# Sheet2.net
KiCad netlist of a schematic drawn in Altium Designer
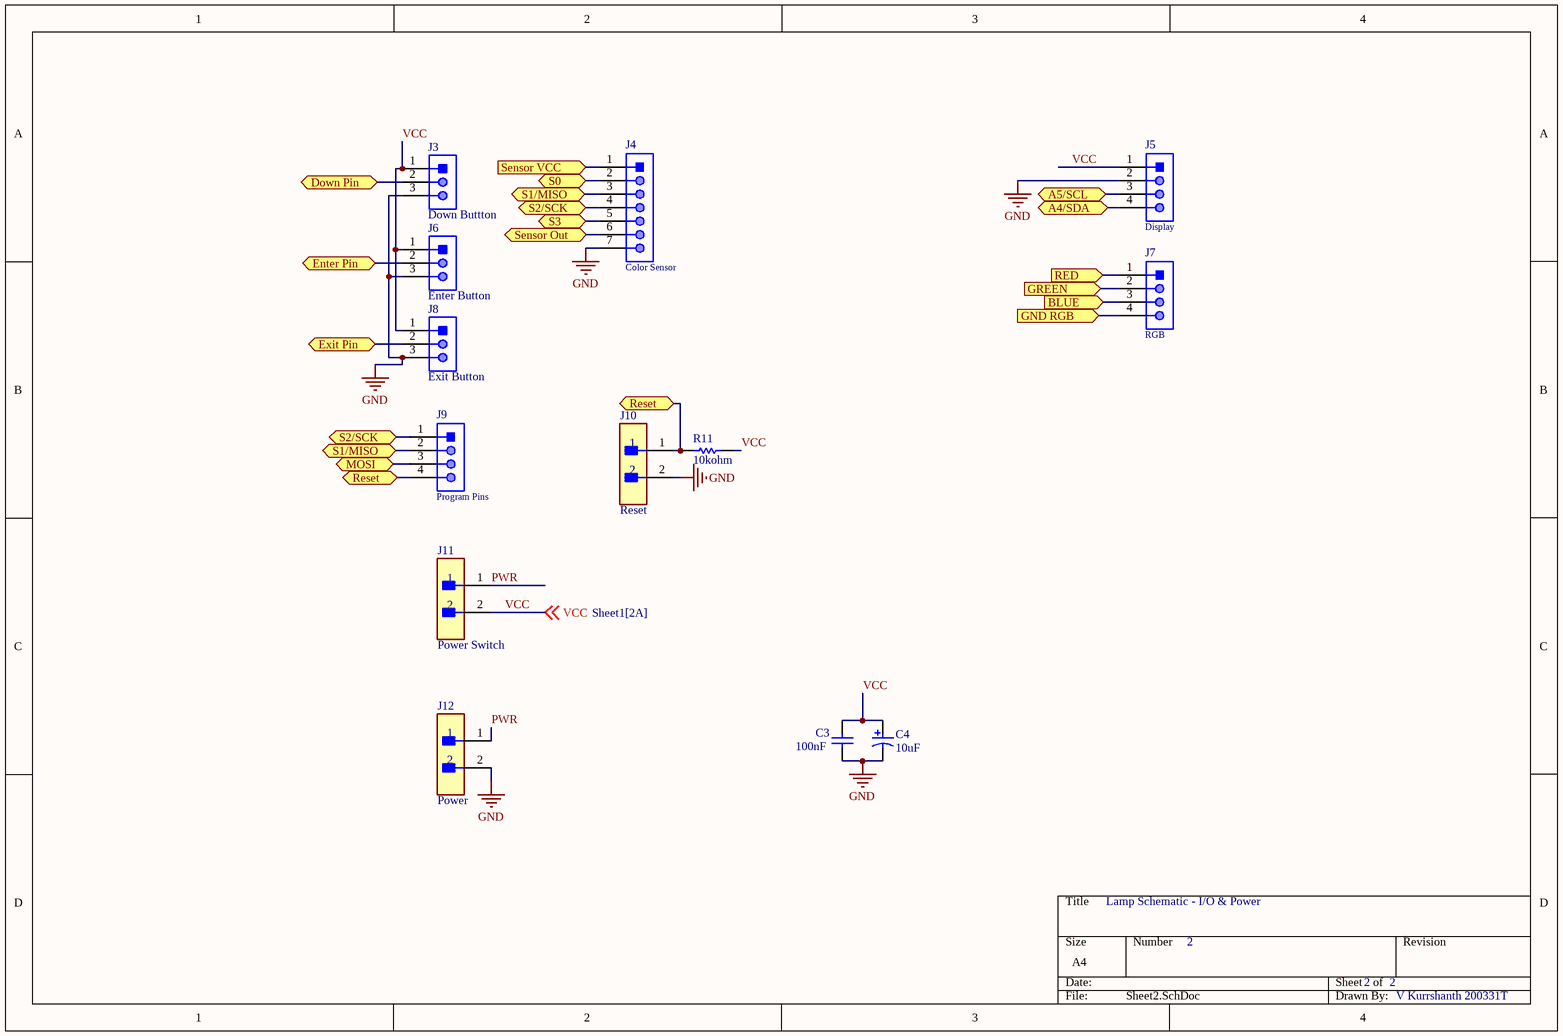
[diagram p0: Sheet2.SchDoc]

(export (version "E")
  (design (tool "Eeschema 10.0.6"))
  (components
    (comp (ref "C3")
      (value "100nF")
      (footprint "VISH-K104K15X7RF5TL2")
      (description "Ceramic Capacitor, 100 nF, +/- 10%, 50 V, -55 to 125 degC, 2-Pin THD, RoHS, Tape and Reel")
      (fields (field (name "MANUFACTURER") "Vishay") (field (name "TOLERANCE") "±10%"))
      (libsource (lib "Altium Content Vault") (part "CAP-NP-2"))
    )
    (comp (ref "C4")
      (value "10uF")
      (footprint "CAPPR55-200-1100X500X1200")
      (description "Aluminum Electrolytic Capacitor, 10 uF, +/- 20%, 50 V, -40 to 85 degC, 2-Pin THD, RoHS, Bulk")
      (fields (field (name "MANUFACTURER") "Panasonic") (field (name "TOLERANCE") "20%"))
      (libsource (lib "Altium Content Vault") (part "CAP-P-2"))
    )
    (comp (ref "J3")
      (value "Down Buttton")
      (footprint "MOLX-22-28-4033_V")
      (description "Male Header, Pitch 2.54 mm, 1 x 3 Position, Height 8.38 mm, Tail Length 3.18 mm, RoHS, Bulk")
      (fields (field (name "MANUFACTURER") "Molex"))
      (libsource (lib "Altium Content Vault") (part "CN-1P-M-R3"))
    )
    (comp (ref "J4")
      (value "Color Sensor")
      (footprint "61300711121")
      (description "THT Vertical Pin Header WR-PHD, Pitch 2.54 mm, Single Row, 7 pins")
      (fields
        (field (name "MANUFACTURER") "Wurth Elektronik")
        (field (name "PART NUMBER") "61300711121")
        (field (name "PUBLISHER") "WurthElektronik")
      )
      (libsource (lib "Altium Content Vault") (part "WE-CN-1P-M-R7"))
    )
    (comp (ref "J5")
      (value "Display")
      (footprint "61300411121")
      (description "THT Vertical Pin Header WR-PHD, Pitch 2.54 mm, Single Row, 4 pins")
      (fields
        (field (name "MANUFACTURER") "Wurth Elektronik")
        (field (name "PART NUMBER") "61300411121")
        (field (name "PUBLISHER") "WurthElektronik")
      )
      (libsource (lib "Altium Content Vault") (part "WE-CN-1P-M-R4"))
    )
    (comp (ref "J6")
      (value "Enter Button")
      (footprint "MOLX-22-28-4033_V")
      (description "Male Header, Pitch 2.54 mm, 1 x 3 Position, Height 8.38 mm, Tail Length 3.18 mm, RoHS, Bulk")
      (fields (field (name "MANUFACTURER") "Molex"))
      (libsource (lib "Altium Content Vault") (part "CN-1P-M-R3"))
    )
    (comp (ref "J7")
      (value "RGB")
      (footprint "61300411121")
      (description "THT Vertical Pin Header WR-PHD, Pitch 2.54 mm, Single Row, 4 pins")
      (fields
        (field (name "MANUFACTURER") "Wurth Elektronik")
        (field (name "PART NUMBER") "61300411121")
        (field (name "PUBLISHER") "WurthElektronik")
      )
      (libsource (lib "Altium Content Vault") (part "WE-CN-1P-M-R4"))
    )
    (comp (ref "J8")
      (value "Exit Button")
      (footprint "MOLX-22-28-4033_V")
      (description "Male Header, Pitch 2.54 mm, 1 x 3 Position, Height 8.38 mm, Tail Length 3.18 mm, RoHS, Bulk")
      (fields (field (name "MANUFACTURER") "Molex"))
      (libsource (lib "Altium Content Vault") (part "CN-1P-M-R3"))
    )
    (comp (ref "J9")
      (value "Program Pins")
      (footprint "61300411121")
      (description "THT Vertical Pin Header WR-PHD, Pitch 2.54 mm, Single Row, 4 pins")
      (fields
        (field (name "MANUFACTURER") "Wurth Elektronik")
        (field (name "PART NUMBER") "61300411121")
        (field (name "PUBLISHER") "WurthElektronik")
      )
      (libsource (lib "Altium Content Vault") (part "WE-CN-1P-M-R4"))
    )
    (comp (ref "J10")
      (value "Reset")
      (footprint "FP-M20-9990246-MFG")
      (description "CONN HEADER VERT 2POS 2.54MM")
      (fields
        (field (name "OCTOPART") "https://octopart.com/m20-9990246-harwin-2590635")
        (field (name "MANUFACTURER") "Harwin")
      )
      (libsource (lib "Altium Content Vault") (part "3bc925449376181038e59eaffc5286c"))
    )
    (comp (ref "J11")
      (value "Power Switch")
      (footprint "FP-M20-9990246-MFG")
      (description "CONN HEADER VERT 2POS 2.54MM")
      (fields
        (field (name "OCTOPART") "https://octopart.com/m20-9990246-harwin-2590635")
        (field (name "MANUFACTURER") "Harwin")
      )
      (libsource (lib "Altium Content Vault") (part "3bc925449376181038e59eaffc5286c"))
    )
    (comp (ref "J12")
      (value "Power")
      (footprint "FP-M20-9990246-MFG")
      (description "CONN HEADER VERT 2POS 2.54MM")
      (fields
        (field (name "OCTOPART") "https://octopart.com/m20-9990246-harwin-2590635")
        (field (name "MANUFACTURER") "Harwin")
      )
      (libsource (lib "Altium Content Vault") (part "3bc925449376181038e59eaffc5286c"))
    )
    (comp (ref "R11")
      (value "10kohm")
      (footprint "RESA60-630X240")
      (description "Axial Resistor, 10 KOhm, +/- 1%, 0.25 W, -55 to 155 degC, 2-Pin THD, RoHS, Bulk")
      (fields (field (name "TOLERANCE") "1%") (field (name "MANUFACTURER") "Yageo"))
      (libsource (lib "Altium Content Vault") (part "RES-2"))
    )
  )
  (nets
    (net (code "1") (name "/A4{slash}SDA") (class "Default")
      (node (ref "J5") (pin "4") (pinfunction "4_4") (pintype "passive"))
    )
    (net (code "2") (name "/A5{slash}SCL") (class "Default")
      (node (ref "J5") (pin "3") (pinfunction "3_3") (pintype "passive"))
    )
    (net (code "3") (name "/BLUE") (class "Default")
      (node (ref "J7") (pin "3") (pinfunction "3_3") (pintype "passive"))
    )
    (net (code "4") (name "/Down Pin") (class "Default")
      (node (ref "J3") (pin "2") (pinfunction "2_2") (pintype "passive"))
    )
    (net (code "5") (name "/Enter Pin") (class "Default")
      (node (ref "J6") (pin "2") (pinfunction "2_2") (pintype "passive"))
    )
    (net (code "6") (name "/Exit Pin") (class "Default")
      (node (ref "J8") (pin "2") (pinfunction "2_2") (pintype "passive"))
    )
    (net (code "7") (name "/GND RGB") (class "Default")
      (node (ref "J7") (pin "4") (pinfunction "4_4") (pintype "passive"))
    )
    (net (code "8") (name "/GREEN") (class "Default")
      (node (ref "J7") (pin "2") (pinfunction "2_2") (pintype "passive"))
    )
    (net (code "9") (name "/MOSI") (class "Default")
      (node (ref "J9") (pin "3") (pinfunction "3_3") (pintype "passive"))
    )
    (net (code "10") (name "/PWR") (class "Default")
      (node (ref "J11") (pin "1") (pinfunction "1_1") (pintype "passive"))
      (node (ref "J12") (pin "1") (pinfunction "1_1") (pintype "passive"))
    )
    (net (code "11") (name "/RED") (class "Default")
      (node (ref "J7") (pin "1") (pinfunction "1_1") (pintype "passive"))
    )
    (net (code "12") (name "/Reset") (class "Default")
      (node (ref "J10") (pin "1") (pinfunction "1_1") (pintype "passive"))
      (node (ref "J9") (pin "4") (pinfunction "4_4") (pintype "passive"))
      (node (ref "R11") (pin "1") (pinfunction "1_1") (pintype "passive"))
    )
    (net (code "13") (name "/S0") (class "Default")
      (node (ref "J4") (pin "2") (pinfunction "2_2") (pintype "passive"))
    )
    (net (code "14") (name "/S1{slash}MISO") (class "Default")
      (node (ref "J4") (pin "3") (pinfunction "3_3") (pintype "passive"))
      (node (ref "J9") (pin "2") (pinfunction "2_2") (pintype "passive"))
    )
    (net (code "15") (name "/S2{slash}SCK") (class "Default")
      (node (ref "J4") (pin "4") (pinfunction "4_4") (pintype "passive"))
      (node (ref "J9") (pin "1") (pinfunction "1_1") (pintype "passive"))
    )
    (net (code "16") (name "/S3") (class "Default")
      (node (ref "J4") (pin "5") (pinfunction "5_5") (pintype "passive"))
    )
    (net (code "17") (name "/Sensor Out") (class "Default")
      (node (ref "J4") (pin "6") (pinfunction "6_6") (pintype "passive"))
    )
    (net (code "18") (name "/Sensor VCC") (class "Default")
      (node (ref "J4") (pin "1") (pinfunction "1_1") (pintype "passive"))
    )
    (net (code "19") (name "GND") (class "Default")
      (node (ref "C3") (pin "1") (pinfunction "1_1") (pintype "passive"))
      (node (ref "C4") (pin "2") (pinfunction "2_2") (pintype "passive"))
      (node (ref "J10") (pin "2") (pinfunction "2_2") (pintype "passive"))
      (node (ref "J12") (pin "2") (pinfunction "2_2") (pintype "passive"))
      (node (ref "J3") (pin "3") (pinfunction "3_3") (pintype "passive"))
      (node (ref "J4") (pin "7") (pinfunction "7_7") (pintype "passive"))
      (node (ref "J5") (pin "2") (pinfunction "2_2") (pintype "passive"))
      (node (ref "J6") (pin "3") (pinfunction "3_3") (pintype "passive"))
      (node (ref "J8") (pin "3") (pinfunction "3_3") (pintype "passive"))
    )
    (net (code "20") (name "VCC") (class "Default")
      (node (ref "C3") (pin "2") (pinfunction "2_2") (pintype "passive"))
      (node (ref "C4") (pin "1") (pinfunction "1_1") (pintype "passive"))
      (node (ref "J11") (pin "2") (pinfunction "2_2") (pintype "passive"))
      (node (ref "J3") (pin "1") (pinfunction "1_1") (pintype "passive"))
      (node (ref "J5") (pin "1") (pinfunction "1_1") (pintype "passive"))
      (node (ref "J6") (pin "1") (pinfunction "1_1") (pintype "passive"))
      (node (ref "J8") (pin "1") (pinfunction "1_1") (pintype "passive"))
      (node (ref "R11") (pin "2") (pinfunction "2_2") (pintype "passive"))
    )
  )
)
